# 17_EDP.net
KiCad netlist of a schematic drawn in Altium Designer
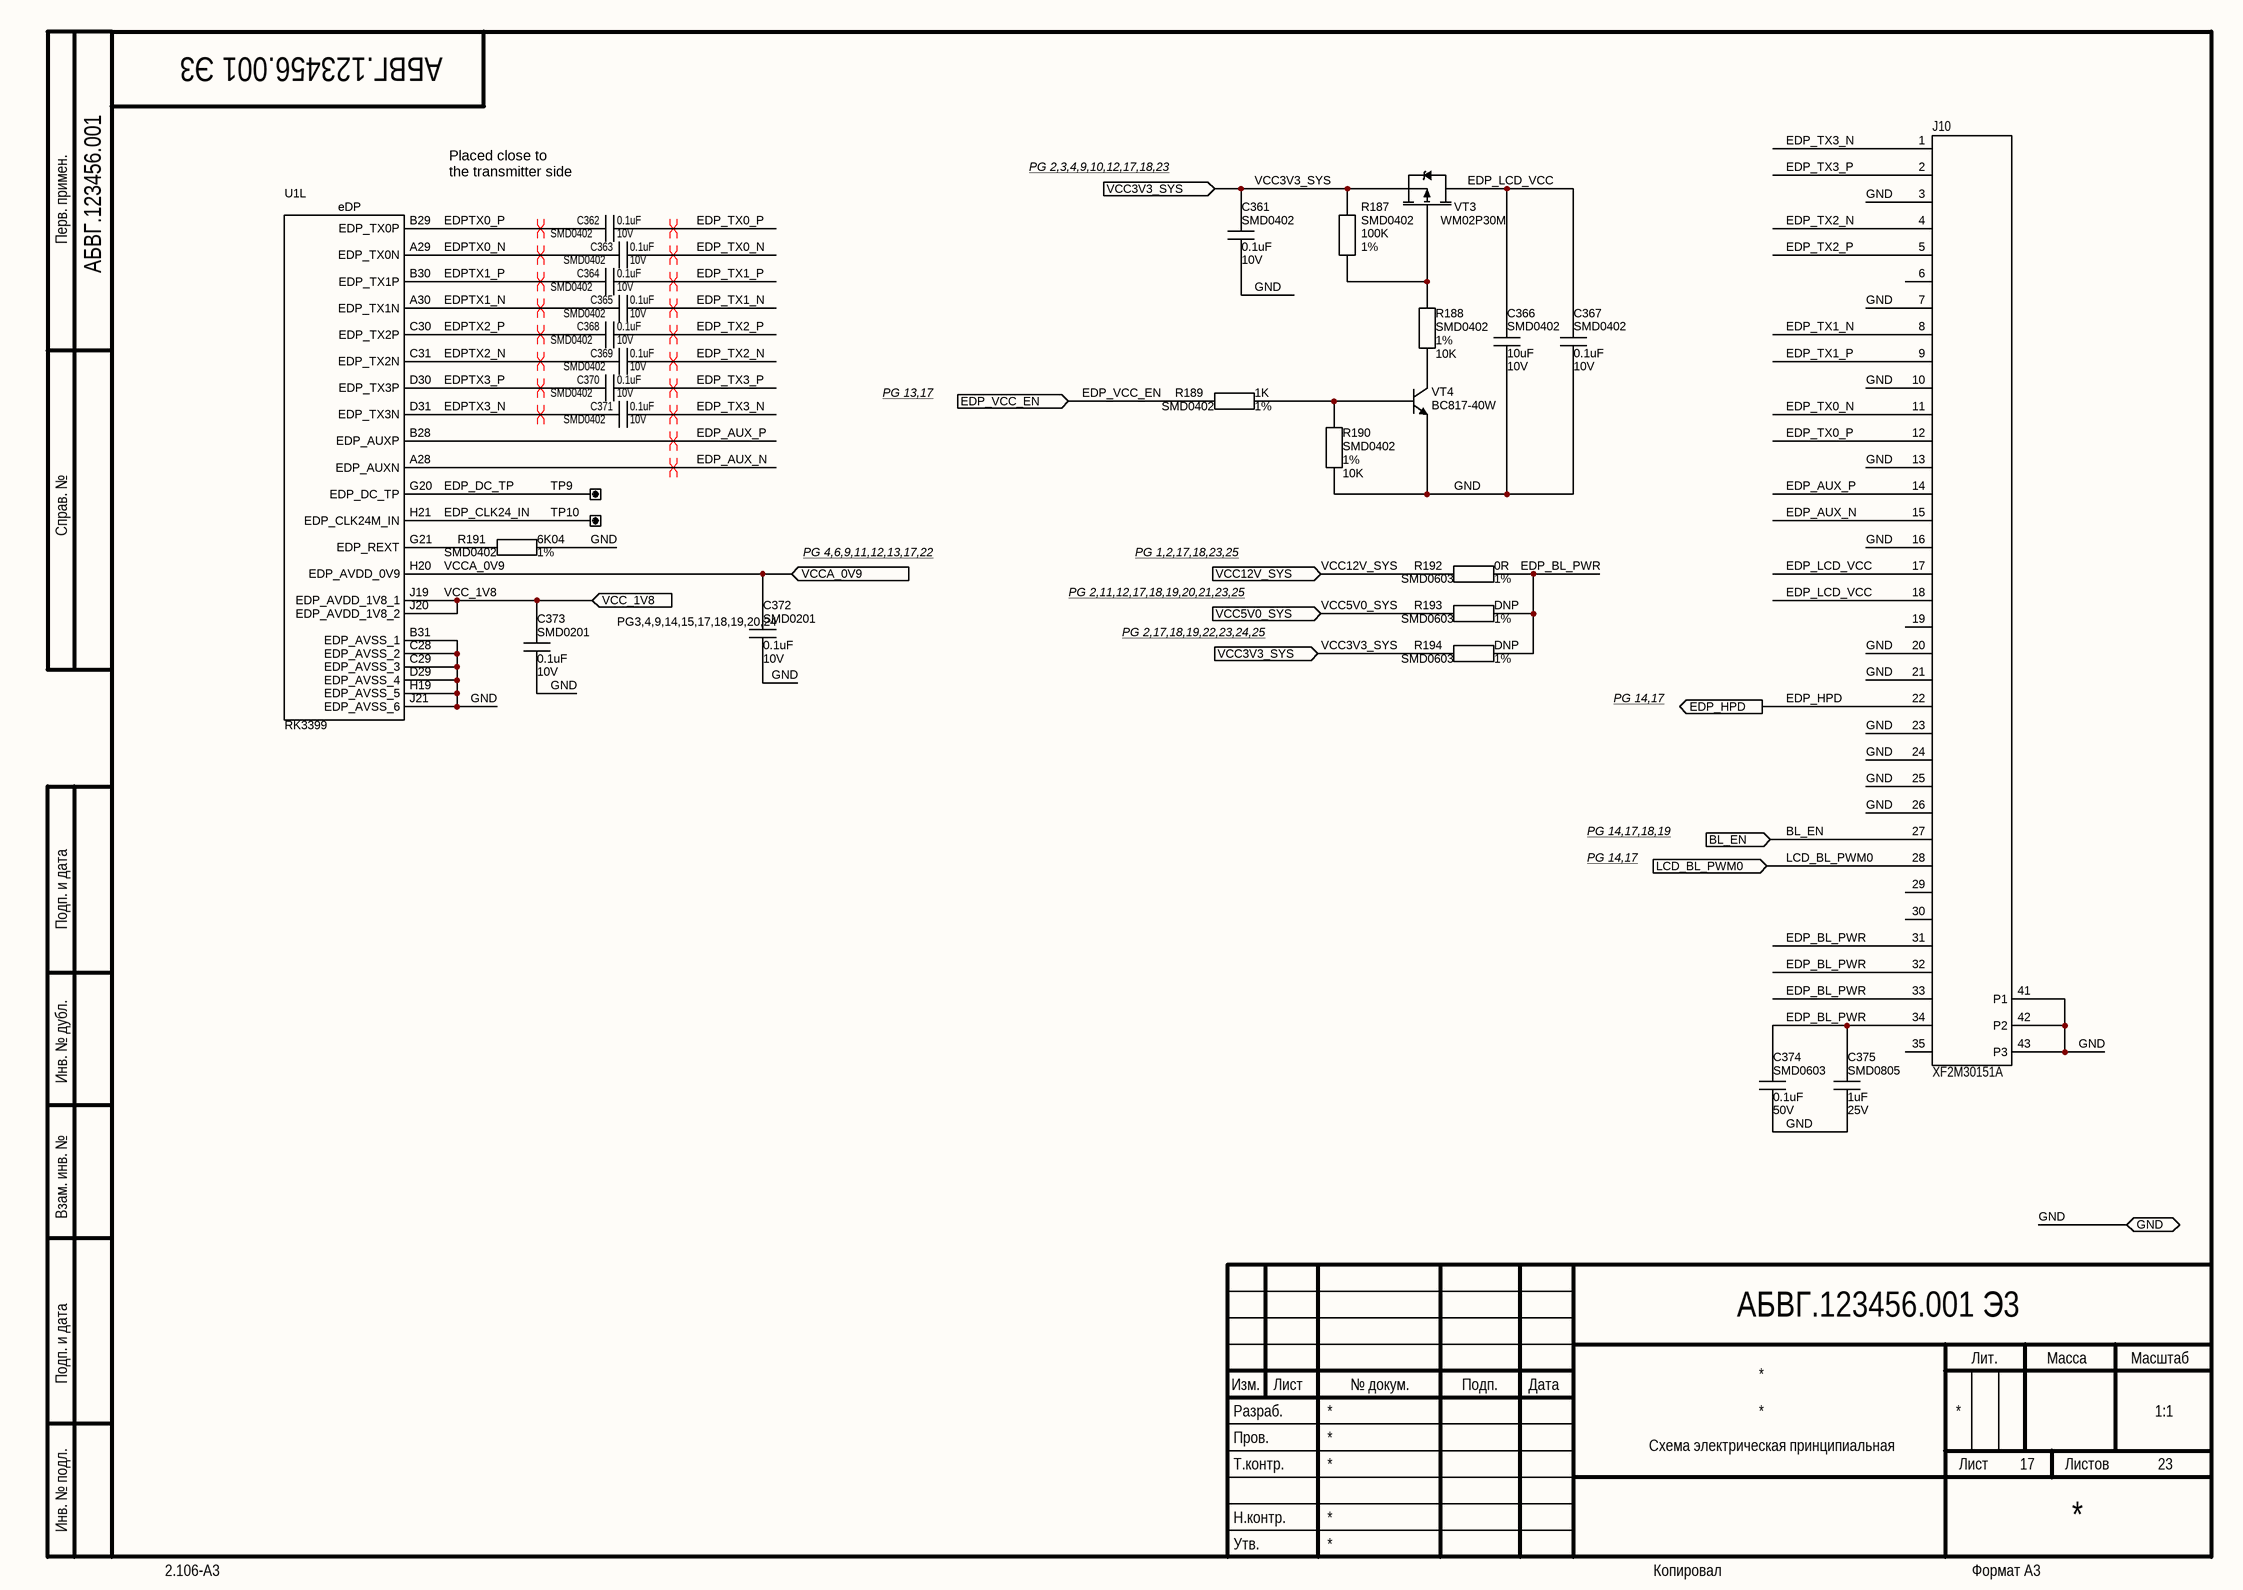
[diagram p0: 17 EDP.SchDoc]

(export (version "E")
  (design (tool "Eeschema 10.0.6"))
  (components
    (comp (ref "C361")
      (value "0.1uF")
      (footprint "Didur_PcbLib_1:CAP_SMD_0402")
      (fields
        (field (name "PACKAGE") "SMD0402")
        (field (name "PARTNUMBER") "CC0402KRX5R6BB104")
        (field (name "VOLTAGE") "10V")
      )
      (libsource (lib "Didur_SchLib_1") (part "Ceramic_Cap"))
    )
    (comp (ref "C362")
      (value "0.1uF")
      (footprint "Didur_PcbLib_1:CAP_SMD_0402_small")
      (fields
        (field (name "PACKAGE") "SMD0402")
        (field (name "PARTNUMBER") "CC0402KRX5R6BB104")
        (field (name "VOLTAGE") "10V")
      )
      (libsource (lib "Didur_SchLib_1") (part "Ceramic_Cap"))
    )
    (comp (ref "C363")
      (value "0.1uF")
      (footprint "Didur_PcbLib_1:CAP_SMD_0402_small")
      (fields
        (field (name "PACKAGE") "SMD0402")
        (field (name "PARTNUMBER") "CC0402KRX5R6BB104")
        (field (name "VOLTAGE") "10V")
      )
      (libsource (lib "Didur_SchLib_1") (part "Ceramic_Cap"))
    )
    (comp (ref "C364")
      (value "0.1uF")
      (footprint "Didur_PcbLib_1:CAP_SMD_0402_small")
      (fields
        (field (name "PACKAGE") "SMD0402")
        (field (name "PARTNUMBER") "CC0402KRX5R6BB104")
        (field (name "VOLTAGE") "10V")
      )
      (libsource (lib "Didur_SchLib_1") (part "Ceramic_Cap"))
    )
    (comp (ref "C365")
      (value "0.1uF")
      (footprint "Didur_PcbLib_1:CAP_SMD_0402_small")
      (fields
        (field (name "PACKAGE") "SMD0402")
        (field (name "PARTNUMBER") "CC0402KRX5R6BB104")
        (field (name "VOLTAGE") "10V")
      )
      (libsource (lib "Didur_SchLib_1") (part "Ceramic_Cap"))
    )
    (comp (ref "C366")
      (value "10uF")
      (footprint "Didur_PcbLib_1:CAP_SMD_0402")
      (fields
        (field (name "PACKAGE") "SMD0402")
        (field (name "PARTNUMBER") "CC0402MRX5R6BB106")
        (field (name "VOLTAGE") "10V")
      )
      (libsource (lib "Didur_SchLib_1") (part "Ceramic_Cap"))
    )
    (comp (ref "C367")
      (value "0.1uF")
      (footprint "Didur_PcbLib_1:CAP_SMD_0402")
      (fields
        (field (name "PACKAGE") "SMD0402")
        (field (name "PARTNUMBER") "CC0402KRX5R6BB104")
        (field (name "VOLTAGE") "10V")
      )
      (libsource (lib "Didur_SchLib_1") (part "Ceramic_Cap"))
    )
    (comp (ref "C368")
      (value "0.1uF")
      (footprint "Didur_PcbLib_1:CAP_SMD_0402_small")
      (fields
        (field (name "PACKAGE") "SMD0402")
        (field (name "PARTNUMBER") "CC0402KRX5R6BB104")
        (field (name "VOLTAGE") "10V")
      )
      (libsource (lib "Didur_SchLib_1") (part "Ceramic_Cap"))
    )
    (comp (ref "C369")
      (value "0.1uF")
      (footprint "Didur_PcbLib_1:CAP_SMD_0402_small")
      (fields
        (field (name "PACKAGE") "SMD0402")
        (field (name "PARTNUMBER") "CC0402KRX5R6BB104")
        (field (name "VOLTAGE") "10V")
      )
      (libsource (lib "Didur_SchLib_1") (part "Ceramic_Cap"))
    )
    (comp (ref "C370")
      (value "0.1uF")
      (footprint "Didur_PcbLib_1:CAP_SMD_0402_small")
      (fields
        (field (name "PACKAGE") "SMD0402")
        (field (name "PARTNUMBER") "CC0402KRX5R6BB104")
        (field (name "VOLTAGE") "10V")
      )
      (libsource (lib "Didur_SchLib_1") (part "Ceramic_Cap"))
    )
    (comp (ref "C371")
      (value "0.1uF")
      (footprint "Didur_PcbLib_1:CAP_SMD_0402_small")
      (fields
        (field (name "PACKAGE") "SMD0402")
        (field (name "PARTNUMBER") "CC0402KRX5R6BB104")
        (field (name "VOLTAGE") "10V")
      )
      (libsource (lib "Didur_SchLib_1") (part "Ceramic_Cap"))
    )
    (comp (ref "C372")
      (value "0.1uF")
      (footprint "Didur_PcbLib_1:CAP_SMD_0201")
      (fields
        (field (name "PACKAGE") "SMD0201")
        (field (name "PARTNUMBER") "CC0201KRX5R6BB104")
        (field (name "VOLTAGE") "10V")
      )
      (libsource (lib "Didur_SchLib_1") (part "Ceramic_Cap"))
    )
    (comp (ref "C373")
      (value "0.1uF")
      (footprint "Didur_PcbLib_1:CAP_SMD_0201")
      (fields
        (field (name "PACKAGE") "SMD0201")
        (field (name "PARTNUMBER") "CC0201KRX5R6BB104")
        (field (name "VOLTAGE") "10V")
      )
      (libsource (lib "Didur_SchLib_1") (part "Ceramic_Cap"))
    )
    (comp (ref "C374")
      (value "0.1uF")
      (footprint "CAP_SMD_0603")
      (fields
        (field (name "PACKAGE") "SMD0603")
        (field (name "PARTNUMBER") "CC0603KRX7R9BB104")
        (field (name "VOLTAGE") "50V")
      )
      (libsource (lib "Didur_SchLib_1") (part "Ceramic_Cap"))
    )
    (comp (ref "C375")
      (value "1uF")
      (footprint "CAP_SMD_0805")
      (fields
        (field (name "PACKAGE") "SMD0805")
        (field (name "PARTNUMBER") "CC0805KKX7R8BB105")
        (field (name "VOLTAGE") "25V")
      )
      (libsource (lib "Didur_SchLib_1") (part "Ceramic_Cap"))
    )
    (comp (ref "J10")
      (value "XF2M30151A")
      (footprint "Didur_PcbLib_1:XF2M-30_3515-1A")
      (libsource (lib "Didur_SchLib_1") (part "LCD_CON_30_35"))
    )
    (comp (ref "R187")
      (value "100K")
      (footprint "Didur_PcbLib_1:RES_SMD_0402")
      (fields
        (field (name "PACKAGE") "SMD0402")
        (field (name "PARTNUMBER") "RC0402FR-07100KL")
        (field (name "TOLERANCE") "1%")
      )
      (libsource (lib "") (part "Chip_Res_2"))
    )
    (comp (ref "R188")
      (value "10K")
      (footprint "Didur_PcbLib_1:RES_SMD_0402")
      (fields
        (field (name "PACKAGE") "SMD0402")
        (field (name "PARTNUMBER") "RC0402FR-0710KL")
        (field (name "TOLERANCE") "1%")
      )
      (libsource (lib "Didur_SchLib_1") (part "Chip_Res"))
    )
    (comp (ref "R189")
      (value "1K")
      (footprint "Didur_PcbLib_1:RES_SMD_0402")
      (fields
        (field (name "PACKAGE") "SMD0402")
        (field (name "PARTNUMBER") "RC0402FR-071KL")
        (field (name "TOLERANCE") "1%")
      )
      (libsource (lib "Didur_SchLib_1") (part "Chip_Res"))
    )
    (comp (ref "R190")
      (value "10K")
      (footprint "Didur_PcbLib_1:RES_SMD_0402")
      (fields
        (field (name "PACKAGE") "SMD0402")
        (field (name "PARTNUMBER") "RC0402FR-0710KL")
        (field (name "TOLERANCE") "1%")
      )
      (libsource (lib "Didur_SchLib_1") (part "Chip_Res"))
    )
    (comp (ref "R191")
      (value "6K04")
      (footprint "Didur_PcbLib_1:RES_SMD_0402")
      (fields
        (field (name "PACKAGE") "SMD0402")
        (field (name "PARTNUMBER") "RC0402FR-076K04L")
        (field (name "TOLERANCE") "1%")
      )
      (libsource (lib "Didur_SchLib_1") (part "Chip_Res"))
    )
    (comp (ref "R192")
      (value "0R")
      (footprint "RES_SMD_0603")
      (fields
        (field (name "PACKAGE") "SMD0603")
        (field (name "PARTNUMBER") "RC0603FR-070RL")
        (field (name "TOLERANCE") "1%")
      )
      (libsource (lib "") (part "Chip_Res_1"))
    )
    (comp (ref "R193")
      (value "DNP")
      (footprint "RES_SMD_0603")
      (fields
        (field (name "PACKAGE") "SMD0603")
        (field (name "PARTNUMBER") "RC0603FR-070RL")
        (field (name "TOLERANCE") "1%")
      )
      (libsource (lib "") (part "Chip_Res_1"))
    )
    (comp (ref "R194")
      (value "DNP")
      (footprint "RES_SMD_0603")
      (fields
        (field (name "PACKAGE") "SMD0603")
        (field (name "PARTNUMBER") "RC0603FR-070RL")
        (field (name "TOLERANCE") "1%")
      )
      (libsource (lib "") (part "Chip_Res_1"))
    )
    (comp (ref "TP9")
      (value "TEST POINT SMD 1MM")
      (footprint "Didur_PcbLib_1:TEST POINT SMD 1MM")
      (libsource (lib "Didur_SchLib_1") (part "TP"))
    )
    (comp (ref "TP10")
      (value "TEST POINT SMD 1MM")
      (footprint "Didur_PcbLib_1:TEST POINT SMD 1MM")
      (libsource (lib "Didur_SchLib_1") (part "TP"))
    )
    (comp (ref "U1")
      (value "RK3399")
      (footprint "BGA828C65P31X31_2100X2100X161N")
      (fields (field (name "Comment") "RK3399_FF"))
      (libsource (lib "Didur_SchLib_1") (part "RK3399_FF"))
    )
    (comp (ref "VT3")
      (value "WM02P30M")
      (footprint "SOT23")
      (fields (field (name "Comment") "Value"))
      (libsource (lib "Didur_SchLib_1") (part "MOSFET_P"))
    )
    (comp (ref "VT4")
      (value "BC817-40W")
      (footprint "Didur_PcbLib_1:SC-70")
      (libsource (lib "Didur_SchLib_1") (part "NPN_BEC"))
    )
  )
  (nets
    (net (code "1") (name "/BL_EN") (class "Default") (node (ref "J10") (pin "27") (pintype "passive")))
    (net (code "2") (name "/EDPTX0_N") (class "Default")
      (node (ref "C363") (pin "2") (pinfunction "2_2") (pintype "power_in"))
      (node (ref "U1") (pin "A29") (pinfunction "EDP_TX0N_A29") (pintype "passive"))
    )
    (net (code "3") (name "/EDPTX0_P") (class "Default")
      (node (ref "C362") (pin "2") (pinfunction "2_2") (pintype "power_in"))
      (node (ref "U1") (pin "B29") (pinfunction "EDP_TX0P_B29") (pintype "passive"))
    )
    (net (code "4") (name "/EDPTX1_N") (class "Default")
      (node (ref "C365") (pin "2") (pinfunction "2_2") (pintype "power_in"))
      (node (ref "U1") (pin "A30") (pinfunction "EDP_TX1N_A30") (pintype "passive"))
    )
    (net (code "5") (name "/EDPTX1_P") (class "Default")
      (node (ref "C364") (pin "2") (pinfunction "2_2") (pintype "power_in"))
      (node (ref "U1") (pin "B30") (pinfunction "EDP_TX1P_B30") (pintype "passive"))
    )
    (net (code "6") (name "/EDPTX2_N") (class "Default")
      (node (ref "C369") (pin "2") (pinfunction "2_2") (pintype "power_in"))
      (node (ref "U1") (pin "C31") (pinfunction "EDP_TX2N_C31") (pintype "passive"))
    )
    (net (code "7") (name "/EDPTX2_P") (class "Default")
      (node (ref "C368") (pin "2") (pinfunction "2_2") (pintype "power_in"))
      (node (ref "U1") (pin "C30") (pinfunction "EDP_TX2P_C30") (pintype "passive"))
    )
    (net (code "8") (name "/EDPTX3_N") (class "Default")
      (node (ref "C371") (pin "2") (pinfunction "2_2") (pintype "power_in"))
      (node (ref "U1") (pin "D31") (pinfunction "EDP_TX3N_D31") (pintype "passive"))
    )
    (net (code "9") (name "/EDPTX3_P") (class "Default")
      (node (ref "C370") (pin "2") (pinfunction "2_2") (pintype "power_in"))
      (node (ref "U1") (pin "D30") (pinfunction "EDP_TX3P_D30") (pintype "passive"))
    )
    (net (code "10") (name "/EDP_AUX_N") (class "Default")
      (node (ref "J10") (pin "15") (pintype "passive"))
      (node (ref "U1") (pin "A28") (pinfunction "EDP_AUXN_A28") (pintype "passive"))
    )
    (net (code "11") (name "/EDP_AUX_P") (class "Default")
      (node (ref "J10") (pin "14") (pintype "passive"))
      (node (ref "U1") (pin "B28") (pinfunction "EDP_AUXP_B28") (pintype "passive"))
    )
    (net (code "12") (name "/EDP_BL_PWR") (class "Default")
      (node (ref "C374") (pin "2") (pinfunction "2_2") (pintype "power_in"))
      (node (ref "C375") (pin "2") (pinfunction "2_2") (pintype "power_in"))
      (node (ref "J10") (pin "31") (pintype "passive"))
      (node (ref "J10") (pin "32") (pintype "passive"))
      (node (ref "J10") (pin "33") (pintype "passive"))
      (node (ref "J10") (pin "34") (pintype "passive"))
      (node (ref "R192") (pin "1") (pinfunction "1_1") (pintype "passive"))
      (node (ref "R193") (pin "1") (pinfunction "1_1") (pintype "passive"))
      (node (ref "R194") (pin "1") (pinfunction "1_1") (pintype "passive"))
    )
    (net (code "13") (name "/EDP_CLK24_IN") (class "Default")
      (node (ref "TP10") (pin "1") (pinfunction "1_1") (pintype "passive"))
      (node (ref "U1") (pin "H21") (pinfunction "EDP_CLK24M_IN_H21") (pintype "passive"))
    )
    (net (code "14") (name "/EDP_DC_TP") (class "Default")
      (node (ref "TP9") (pin "1") (pinfunction "1_1") (pintype "passive"))
      (node (ref "U1") (pin "G20") (pinfunction "EDP_DC_TP_G20") (pintype "passive"))
    )
    (net (code "15") (name "/EDP_HPD") (class "Default") (node (ref "J10") (pin "22") (pintype "passive")))
    (net (code "16") (name "/EDP_LCD_VCC") (class "Default")
      (node (ref "C366") (pin "1") (pinfunction "1_1") (pintype "power_in"))
      (node (ref "C367") (pin "1") (pinfunction "1_1") (pintype "power_in"))
      (node (ref "J10") (pin "17") (pintype "passive"))
      (node (ref "J10") (pin "18") (pintype "passive"))
      (node (ref "VT3") (pin "3") (pinfunction "D_3") (pintype "passive"))
    )
    (net (code "17") (name "/EDP_TX0_N") (class "Default")
      (node (ref "C363") (pin "1") (pinfunction "1_1") (pintype "power_in"))
      (node (ref "J10") (pin "11") (pintype "passive"))
    )
    (net (code "18") (name "/EDP_TX0_P") (class "Default")
      (node (ref "C362") (pin "1") (pinfunction "1_1") (pintype "power_in"))
      (node (ref "J10") (pin "12") (pintype "passive"))
    )
    (net (code "19") (name "/EDP_TX1_N") (class "Default")
      (node (ref "C365") (pin "1") (pinfunction "1_1") (pintype "power_in"))
      (node (ref "J10") (pin "8") (pintype "passive"))
    )
    (net (code "20") (name "/EDP_TX1_P") (class "Default")
      (node (ref "C364") (pin "1") (pinfunction "1_1") (pintype "power_in"))
      (node (ref "J10") (pin "9") (pintype "passive"))
    )
    (net (code "21") (name "/EDP_TX2_N") (class "Default")
      (node (ref "C369") (pin "1") (pinfunction "1_1") (pintype "power_in"))
      (node (ref "J10") (pin "4") (pintype "passive"))
    )
    (net (code "22") (name "/EDP_TX2_P") (class "Default")
      (node (ref "C368") (pin "1") (pinfunction "1_1") (pintype "power_in"))
      (node (ref "J10") (pin "5") (pintype "passive"))
    )
    (net (code "23") (name "/EDP_TX3_N") (class "Default")
      (node (ref "C371") (pin "1") (pinfunction "1_1") (pintype "power_in"))
      (node (ref "J10") (pin "1") (pintype "passive"))
    )
    (net (code "24") (name "/EDP_TX3_P") (class "Default")
      (node (ref "C370") (pin "1") (pinfunction "1_1") (pintype "power_in"))
      (node (ref "J10") (pin "2") (pintype "passive"))
    )
    (net (code "25") (name "/EDP_VCC_EN") (class "Default")
      (node (ref "R189") (pin "1") (pinfunction "1_1") (pintype "passive"))
    )
    (net (code "26") (name "/GND") (class "Default")
      (node (ref "C361") (pin "2") (pinfunction "2_2") (pintype "power_in"))
      (node (ref "C366") (pin "2") (pinfunction "2_2") (pintype "power_in"))
      (node (ref "C367") (pin "2") (pinfunction "2_2") (pintype "power_in"))
      (node (ref "C372") (pin "2") (pinfunction "2_2") (pintype "power_in"))
      (node (ref "C373") (pin "2") (pinfunction "2_2") (pintype "power_in"))
      (node (ref "C374") (pin "1") (pinfunction "1_1") (pintype "power_in"))
      (node (ref "C375") (pin "1") (pinfunction "1_1") (pintype "power_in"))
      (node (ref "J10") (pin "10") (pintype "passive"))
      (node (ref "J10") (pin "13") (pintype "passive"))
      (node (ref "J10") (pin "16") (pintype "passive"))
      (node (ref "J10") (pin "20") (pintype "passive"))
      (node (ref "J10") (pin "21") (pintype "passive"))
      (node (ref "J10") (pin "23") (pintype "passive"))
      (node (ref "J10") (pin "24") (pintype "passive"))
      (node (ref "J10") (pin "25") (pintype "passive"))
      (node (ref "J10") (pin "26") (pintype "passive"))
      (node (ref "J10") (pin "3") (pintype "passive"))
      (node (ref "J10") (pin "41") (pinfunction "P1_41") (pintype "passive"))
      (node (ref "J10") (pin "42") (pinfunction "P2_42") (pintype "passive"))
      (node (ref "J10") (pin "43") (pinfunction "P3_43") (pintype "passive"))
      (node (ref "J10") (pin "7") (pintype "passive"))
      (node (ref "R190") (pin "1") (pinfunction "1_1") (pintype "passive"))
      (node (ref "R191") (pin "2") (pinfunction "2_2") (pintype "passive"))
      (node (ref "U1") (pin "B31") (pinfunction "EDP_AVSS_1_B31") (pintype "passive"))
      (node (ref "U1") (pin "C28") (pinfunction "EDP_AVSS_2_C28") (pintype "passive"))
      (node (ref "U1") (pin "C29") (pinfunction "EDP_AVSS_3_C29") (pintype "passive"))
      (node (ref "U1") (pin "D29") (pinfunction "EDP_AVSS_4_D29") (pintype "passive"))
      (node (ref "U1") (pin "H19") (pinfunction "EDP_AVSS_5_H19") (pintype "passive"))
      (node (ref "U1") (pin "J21") (pinfunction "EDP_AVSS_6_J21") (pintype "passive"))
      (node (ref "VT4") (pin "2") (pinfunction "E_2") (pintype "passive"))
    )
    (net (code "27") (name "/LCD_BL_PWM0") (class "Default")
      (node (ref "J10") (pin "28") (pintype "passive"))
    )
    (net (code "28") (name "/VCC3V3_SYS") (class "Default")
      (node (ref "C361") (pin "1") (pinfunction "1_1") (pintype "power_in"))
      (node (ref "R187") (pin "2") (pinfunction "2_2") (pintype "passive"))
      (node (ref "R194") (pin "2") (pinfunction "2_2") (pintype "passive"))
      (node (ref "VT3") (pin "2") (pinfunction "S_2") (pintype "passive"))
    )
    (net (code "29") (name "/VCC5V0_SYS") (class "Default")
      (node (ref "R193") (pin "2") (pinfunction "2_2") (pintype "passive"))
    )
    (net (code "30") (name "/VCC12V_SYS") (class "Default")
      (node (ref "R192") (pin "2") (pinfunction "2_2") (pintype "passive"))
    )
    (net (code "31") (name "/VCCA_0V9") (class "Default")
      (node (ref "C372") (pin "1") (pinfunction "1_1") (pintype "power_in"))
      (node (ref "U1") (pin "H20") (pinfunction "EDP_AVDD_0V9_H20") (pintype "passive"))
    )
    (net (code "32") (name "/VCC_1V8") (class "Default")
      (node (ref "C373") (pin "1") (pinfunction "1_1") (pintype "power_in"))
      (node (ref "U1") (pin "J19") (pinfunction "EDP_AVDD_1V8_1_J19") (pintype "passive"))
      (node (ref "U1") (pin "J20") (pinfunction "EDP_AVDD_1V8_2_J20") (pintype "passive"))
    )
    (net (code "33") (name "Net-(U1L-EDP_REXT)") (class "Default")
      (node (ref "R191") (pin "1") (pinfunction "1_1") (pintype "passive"))
      (node (ref "U1") (pin "G21") (pinfunction "EDP_REXT_G21") (pintype "passive"))
    )
    (net (code "34") (name "Net-(VT3-G)") (class "Default")
      (node (ref "R187") (pin "1") (pinfunction "1_1") (pintype "passive"))
      (node (ref "R188") (pin "2") (pinfunction "2_2") (pintype "passive"))
      (node (ref "VT3") (pin "1") (pinfunction "G_1") (pintype "passive"))
    )
    (net (code "35") (name "Net-(VT4-B)") (class "Default")
      (node (ref "R189") (pin "2") (pinfunction "2_2") (pintype "passive"))
      (node (ref "R190") (pin "2") (pinfunction "2_2") (pintype "passive"))
      (node (ref "VT4") (pin "1") (pinfunction "B_1") (pintype "passive"))
    )
    (net (code "36") (name "Net-(VT4-C)") (class "Default")
      (node (ref "R188") (pin "1") (pinfunction "1_1") (pintype "passive"))
      (node (ref "VT4") (pin "3") (pinfunction "C_3") (pintype "passive"))
    )
    (net (code "37") (name "unconnected-(J10-Pad6)") (class "Default")
      (node (ref "J10") (pin "6") (pintype "passive"))
    )
    (net (code "38") (name "unconnected-(J10-Pad19)") (class "Default")
      (node (ref "J10") (pin "19") (pintype "passive"))
    )
    (net (code "39") (name "unconnected-(J10-Pad29)") (class "Default")
      (node (ref "J10") (pin "29") (pintype "passive"))
    )
    (net (code "40") (name "unconnected-(J10-Pad30)") (class "Default")
      (node (ref "J10") (pin "30") (pintype "passive"))
    )
    (net (code "41") (name "unconnected-(J10-Pad35)") (class "Default")
      (node (ref "J10") (pin "35") (pintype "passive"))
    )
  )
)
